# RocketometerPx_9150.net
KiCad netlist of a schematic drawn in EAGLE
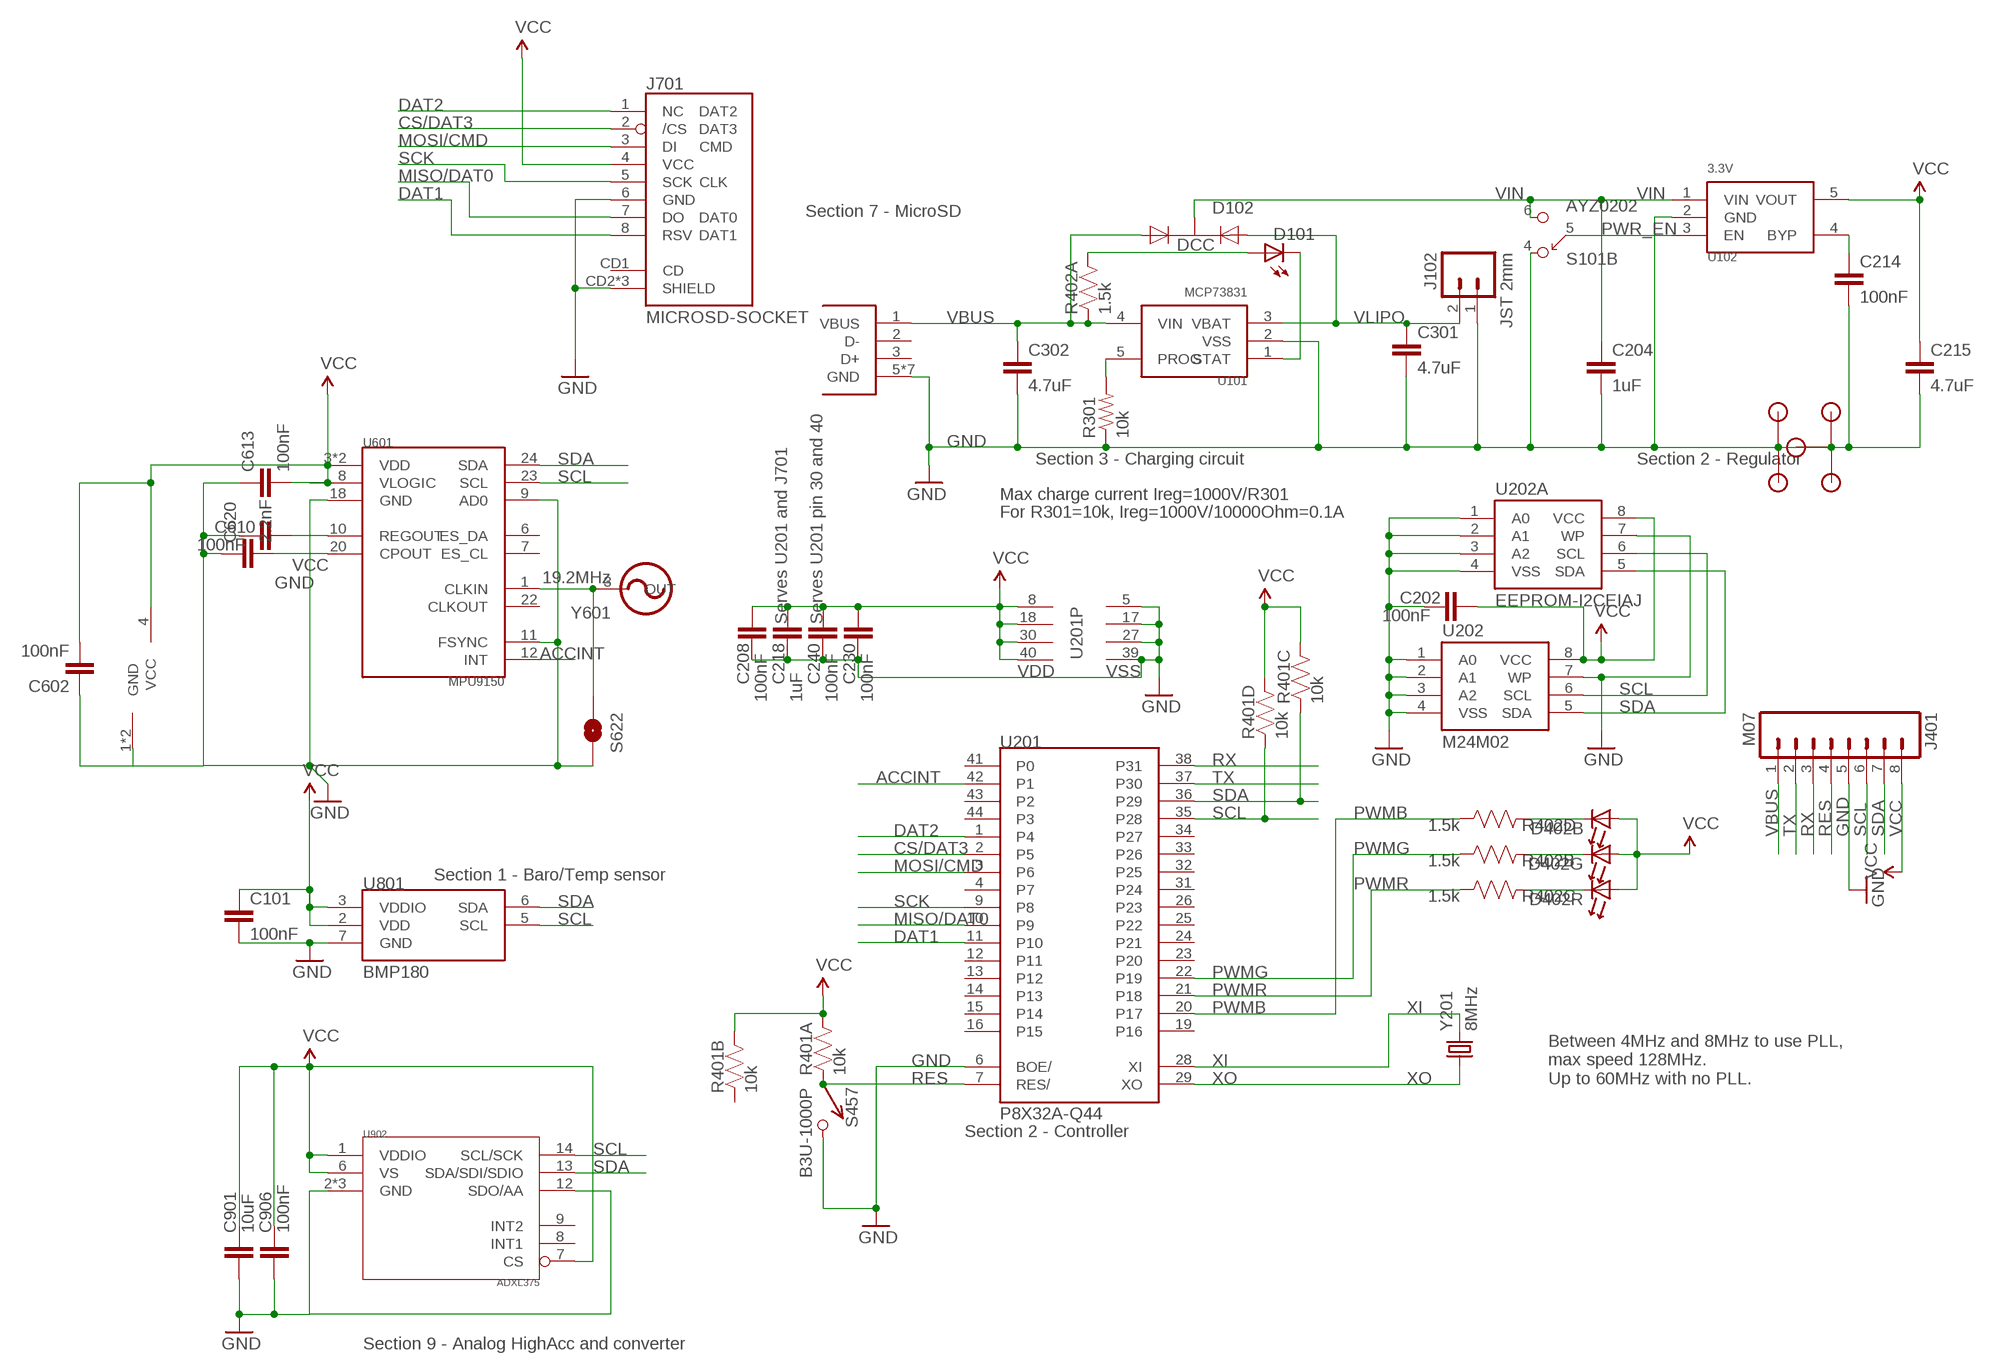
[diagram p0: schematic, sheet 1]

(export (version "E")
  (design (tool "Eeschema 10.0.6"))
  (components
    (comp (ref "C101")
      (value "100nF")
      (footprint "eagle-import:0402-CAP")
      (libsource (lib "eagle-import") (part "CAP0402-CAP"))
    )
    (comp (ref "C202")
      (value "100nF")
      (footprint "eagle-import:0402-CAP")
      (libsource (lib "eagle-import") (part "CAP0402-CAP"))
    )
    (comp (ref "C204")
      (value "1uF")
      (footprint "eagle-import:0402-CAP")
      (libsource (lib "eagle-import") (part "CAP0402-CAP"))
    )
    (comp (ref "C208")
      (value "100nF")
      (footprint "eagle-import:0402-CAP")
      (libsource (lib "eagle-import") (part "CAP0402-CAP"))
    )
    (comp (ref "C214")
      (value "100nF")
      (footprint "eagle-import:0402-CAP")
      (libsource (lib "eagle-import") (part "CAP0402-CAP"))
    )
    (comp (ref "C215")
      (value "4.7uF")
      (footprint "eagle-import:0402-CAP")
      (libsource (lib "eagle-import") (part "CAP0402-CAP"))
    )
    (comp (ref "C218")
      (value "1uF")
      (footprint "eagle-import:0402-CAP")
      (libsource (lib "eagle-import") (part "CAP0402-CAP"))
    )
    (comp (ref "C230")
      (value "100nF")
      (footprint "eagle-import:0402-CAP")
      (libsource (lib "eagle-import") (part "CAP0402-CAP"))
    )
    (comp (ref "C240")
      (value "100nF")
      (footprint "eagle-import:0402-CAP")
      (libsource (lib "eagle-import") (part "CAP0402-CAP"))
    )
    (comp (ref "C301")
      (value "4.7uF")
      (footprint "eagle-import:0402-CAP")
      (libsource (lib "eagle-import") (part "CAP0402-CAP"))
    )
    (comp (ref "C302")
      (value "4.7uF")
      (footprint "eagle-import:0402-CAP")
      (libsource (lib "eagle-import") (part "CAP0402-CAP"))
    )
    (comp (ref "C602")
      (value "100nF")
      (footprint "eagle-import:0402-CAP")
      (libsource (lib "eagle-import") (part "CAP0402-CAP"))
    )
    (comp (ref "C610")
      (value "100nF")
      (footprint "eagle-import:0402-CAP")
      (libsource (lib "eagle-import") (part "CAP0402-CAP"))
    )
    (comp (ref "C613")
      (value "100nF")
      (footprint "eagle-import:0402-CAP")
      (libsource (lib "eagle-import") (part "CAP0402-CAP"))
    )
    (comp (ref "C620")
      (value "2.2nF")
      (footprint "eagle-import:0402-CAP")
      (libsource (lib "eagle-import") (part "CAP0402-CAP"))
    )
    (comp (ref "C901")
      (value "10uF")
      (footprint "eagle-import:0603-CAP")
      (libsource (lib "eagle-import") (part "CAP0603-CAP"))
    )
    (comp (ref "C906")
      (value "100nF")
      (footprint "eagle-import:0402-CAP")
      (libsource (lib "eagle-import") (part "SparkFun-Passives_CAP0402-CAP"))
    )
    (comp (ref "D101")
      (value "YELLOW")
      (footprint "eagle-import:LED-0603")
      (libsource (lib "eagle-import") (part "LED0603"))
    )
    (comp (ref "D102")
      (value "DCC")
      (footprint "eagle-import:SOT-23-3")
      (libsource (lib "eagle-import") (part "PMEG2005CT"))
    )
    (comp (ref "D402")
      (value "SMLP36RGB2W(R)")
      (footprint "eagle-import:SMLP36")
      (libsource (lib "eagle-import") (part "SMLP36RGB2W(R)"))
    )
    (comp (ref "J101")
      (value "USB_MICROB_JSTGCT")
      (footprint "eagle-import:USB_MICROB_3075")
      (libsource (lib "eagle-import") (part "USB_MICROB_JSTGCT"))
    )
    (comp (ref "J102")
      (value "JST 2mm")
      (footprint "eagle-import:JST-2-SMD")
      (libsource (lib "eagle-import") (part "M02-JST-2MM-SMT"))
    )
    (comp (ref "J401")
      (value "M07")
      (footprint "eagle-import:1X08")
      (libsource (lib "eagle-import") (part "M081X08"))
    )
    (comp (ref "J701")
      (value "MICROSD-SOCKET")
      (footprint "eagle-import:MICROSD-SOCKET-PP")
      (libsource (lib "eagle-import") (part "MICROSD-SOCKET"))
    )
    (comp (ref "JP1")
      (value "STANDOFF")
      (footprint "eagle-import:STANDOFF")
      (libsource (lib "eagle-import") (part "STANDOFF"))
    )
    (comp (ref "JP2")
      (value "STANDOFF")
      (footprint "eagle-import:STANDOFF")
      (libsource (lib "eagle-import") (part "STANDOFF"))
    )
    (comp (ref "JP3")
      (value "STANDOFF")
      (footprint "eagle-import:STANDOFF")
      (libsource (lib "eagle-import") (part "STANDOFF"))
    )
    (comp (ref "JP4")
      (value "STANDOFF")
      (footprint "eagle-import:STANDOFF")
      (libsource (lib "eagle-import") (part "STANDOFF"))
    )
    (comp (ref "JP5")
      (value "STANDOFF")
      (footprint "eagle-import:STANDOFF")
      (libsource (lib "eagle-import") (part "STANDOFF"))
    )
    (comp (ref "R301")
      (value "10k")
      (footprint "eagle-import:0402-RES")
      (libsource (lib "eagle-import") (part "RESISTOR0402-RES"))
    )
    (comp (ref "R401")
      (value "10k")
      (footprint "eagle-import:CRA04")
      (fields (field (name "DIGIKEY") "CRA4S810KCT-ND"))
      (libsource (lib "eagle-import") (part "RP404"))
    )
    (comp (ref "R402")
      (value "1.5k")
      (footprint "eagle-import:CRA04")
      (fields (field (name "DIGIKEY") "CRA4S81.5KCT-ND"))
      (libsource (lib "eagle-import") (part "RP404"))
    )
    (comp (ref "S101")
      (value "AYZ0202")
      (footprint "eagle-import:AYZ0202")
      (libsource (lib "eagle-import") (part "AYZ0202"))
    )
    (comp (ref "S457")
      (value "B3U-1000P")
      (footprint "eagle-import:B3U-1000P")
      (libsource (lib "eagle-import") (part "B3U-1000P"))
    )
    (comp (ref "S622")
      (value "SOLDERJUMPERNO")
      (footprint "eagle-import:SJ_2S-NO")
      (libsource (lib "eagle-import") (part "SOLDERJUMPERNO"))
    )
    (comp (ref "U101")
      (value "MCP73831")
      (footprint "eagle-import:SOT-23-5")
      (libsource (lib "eagle-import") (part "MCP73831"))
    )
    (comp (ref "U102")
      (value "3.3V")
      (footprint "eagle-import:SOT-23-5")
      (libsource (lib "eagle-import") (part "MIC5319D5"))
    )
    (comp (ref "U201")
      (value "P8X32A-Q44")
      (footprint "eagle-import:P8X32A-Q44")
      (fields (field (name "DIGIKEY") "P8X32A-Q44-ND"))
      (libsource (lib "eagle-import") (part "P8X32A-Q44"))
    )
    (comp (ref "U202")
      (value "M24M02")
      (footprint "eagle-import:SO8N")
      (libsource (lib "eagle-import") (part "EEPROM-I2C"))
    )
    (comp (ref "U202A")
      (value "EEPROM-I2CEIAJ")
      (footprint "eagle-import:SO08-EIAJ")
      (libsource (lib "eagle-import") (part "EEPROM-I2CEIAJ"))
    )
    (comp (ref "U601")
      (value "MPU9150")
      (footprint "eagle-import:MPU60X0")
      (libsource (lib "eagle-import") (part "MPU6050"))
    )
    (comp (ref "U801")
      (value "BMP180")
      (footprint "eagle-import:BMP180")
      (libsource (lib "eagle-import") (part "BMP180"))
    )
    (comp (ref "U902")
      (value "ADXL375")
      (footprint "eagle-import:ADXL375")
      (libsource (lib "eagle-import") (part "ADXL375"))
    )
    (comp (ref "Y201")
      (value "8MHz")
      (footprint "eagle-import:CRYSTAL_SMD_3_2MM_2_5MM")
      (libsource (lib "eagle-import") (part "NX3225GD"))
    )
    (comp (ref "Y601")
      (value "19.2MHz")
      (footprint "eagle-import:CRYSTAL_SMD_5MM_3_2MM")
      (libsource (lib "eagle-import") (part "OSCILLATORM532"))
    )
  )
  (nets
    (net (code "1") (name "/ACCINT") (class "Default")
      (node (ref "U201") (pin "42") (pinfunction "P1_42") (pintype "bidirectional"))
      (node (ref "U601") (pin "12") (pinfunction "INT_12") (pintype "bidirectional"))
    )
    (net (code "2") (name "/CS{slash}DAT3") (class "Default")
      (node (ref "J701") (pin "2") (pinfunction "/CS_2") (pintype "bidirectional"))
      (node (ref "U201") (pin "2") (pinfunction "P5_2") (pintype "bidirectional"))
    )
    (net (code "3") (name "/DAT1") (class "Default")
      (node (ref "J701") (pin "8") (pinfunction "RSV_8") (pintype "bidirectional"))
      (node (ref "U201") (pin "11") (pinfunction "P10_11") (pintype "bidirectional"))
    )
    (net (code "4") (name "/DAT2") (class "Default")
      (node (ref "J701") (pin "1") (pinfunction "NC_1") (pintype "bidirectional"))
      (node (ref "U201") (pin "1") (pinfunction "P4_1") (pintype "bidirectional"))
    )
    (net (code "5") (name "/MISO{slash}DAT0") (class "Default")
      (node (ref "J701") (pin "7") (pinfunction "DO_7") (pintype "bidirectional"))
      (node (ref "U201") (pin "10") (pinfunction "P9_10") (pintype "bidirectional"))
    )
    (net (code "6") (name "/MOSI{slash}CMD") (class "Default")
      (node (ref "J701") (pin "3") (pinfunction "DI_3") (pintype "bidirectional"))
      (node (ref "U201") (pin "3") (pinfunction "P6_3") (pintype "bidirectional"))
    )
    (net (code "7") (name "/PWMB") (class "Default")
      (node (ref "R402") (pin "4") (pinfunction "1_4") (pintype "passive"))
      (node (ref "U201") (pin "20") (pinfunction "P17_20") (pintype "bidirectional"))
    )
    (net (code "8") (name "/PWMG") (class "Default")
      (node (ref "R402") (pin "2") (pinfunction "1_2") (pintype "passive"))
      (node (ref "U201") (pin "22") (pinfunction "P19_22") (pintype "bidirectional"))
    )
    (net (code "9") (name "/PWMR") (class "Default")
      (node (ref "R402") (pin "3") (pinfunction "1_3") (pintype "passive"))
      (node (ref "U201") (pin "21") (pinfunction "P18_21") (pintype "bidirectional"))
    )
    (net (code "10") (name "/PWR_EN") (class "Default")
      (node (ref "S101") (pin "5") (pinfunction "P$3_5") (pintype "bidirectional"))
      (node (ref "U102") (pin "3") (pinfunction "EN_3") (pintype "bidirectional"))
    )
    (net (code "11") (name "/RES") (class "Default")
      (node (ref "J401") (pin "4") (pinfunction "4_4") (pintype "passive"))
      (node (ref "R401") (pin "1") (pinfunction "1_1") (pintype "passive"))
      (node (ref "S457") (pin "P$1") (pinfunction "1_P$1") (pintype "bidirectional"))
      (node (ref "U201") (pin "7") (pinfunction "RES/_7") (pintype "bidirectional"))
    )
    (net (code "12") (name "/RX") (class "Default")
      (node (ref "J401") (pin "3") (pinfunction "3_3") (pintype "passive"))
      (node (ref "U201") (pin "38") (pinfunction "P31_38") (pintype "bidirectional"))
    )
    (net (code "13") (name "/SCK") (class "Default")
      (node (ref "J701") (pin "5") (pinfunction "SCK_5") (pintype "bidirectional"))
      (node (ref "U201") (pin "9") (pinfunction "P8_9") (pintype "bidirectional"))
    )
    (net (code "14") (name "/SCL") (class "Default")
      (node (ref "J401") (pin "6") (pinfunction "6_6") (pintype "passive"))
      (node (ref "R401") (pin "4") (pinfunction "1_4") (pintype "passive"))
      (node (ref "U201") (pin "35") (pinfunction "P28_35") (pintype "bidirectional"))
      (node (ref "U202") (pin "6") (pinfunction "SCL_6") (pintype "bidirectional"))
      (node (ref "U202A") (pin "6") (pinfunction "SCL_6") (pintype "bidirectional"))
      (node (ref "U601") (pin "23") (pinfunction "SCL_23") (pintype "bidirectional"))
      (node (ref "U801") (pin "5") (pinfunction "SCL_5") (pintype "input"))
      (node (ref "U902") (pin "14") (pinfunction "SCL/SCK_14") (pintype "input"))
    )
    (net (code "15") (name "/SDA") (class "Default")
      (node (ref "J401") (pin "7") (pinfunction "7_7") (pintype "passive"))
      (node (ref "R401") (pin "3") (pinfunction "1_3") (pintype "passive"))
      (node (ref "U201") (pin "36") (pinfunction "P29_36") (pintype "bidirectional"))
      (node (ref "U202") (pin "5") (pinfunction "SDA_5") (pintype "bidirectional"))
      (node (ref "U202A") (pin "5") (pinfunction "SDA_5") (pintype "bidirectional"))
      (node (ref "U601") (pin "24") (pinfunction "SDA_24") (pintype "bidirectional"))
      (node (ref "U801") (pin "6") (pinfunction "SDA_6") (pintype "bidirectional"))
      (node (ref "U902") (pin "13") (pinfunction "SDA/SDI/SDIO_13") (pintype "bidirectional"))
    )
    (net (code "16") (name "/TX") (class "Default")
      (node (ref "J401") (pin "2") (pinfunction "2_2") (pintype "passive"))
      (node (ref "U201") (pin "37") (pinfunction "P30_37") (pintype "bidirectional"))
    )
    (net (code "17") (name "/VBUS") (class "Default")
      (node (ref "C302") (pin "1") (pinfunction "1_1") (pintype "passive"))
      (node (ref "D102") (pin "1") (pinfunction "A1_1") (pintype "passive"))
      (node (ref "J101") (pin "1") (pinfunction "VBUS_1") (pintype "bidirectional"))
      (node (ref "J401") (pin "1") (pinfunction "1_1") (pintype "passive"))
      (node (ref "R402") (pin "1") (pinfunction "1_1") (pintype "passive"))
      (node (ref "U101") (pin "4") (pinfunction "VIN_4") (pintype "power_in"))
    )
    (net (code "18") (name "/VIN") (class "Default")
      (node (ref "C204") (pin "1") (pinfunction "1_1") (pintype "passive"))
      (node (ref "D102") (pin "3") (pinfunction "K_3") (pintype "passive"))
      (node (ref "S101") (pin "6") (pinfunction "P$2_6") (pintype "bidirectional"))
      (node (ref "U102") (pin "1") (pinfunction "VIN_1") (pintype "bidirectional"))
    )
    (net (code "19") (name "/VLIPO") (class "Default")
      (node (ref "C301") (pin "1") (pinfunction "1_1") (pintype "passive"))
      (node (ref "D102") (pin "2") (pinfunction "A2_2") (pintype "passive"))
      (node (ref "J102") (pin "2") (pinfunction "2_2") (pintype "passive"))
      (node (ref "U101") (pin "3") (pinfunction "VBAT_3") (pintype "power_in"))
    )
    (net (code "20") (name "/XI") (class "Default")
      (node (ref "U201") (pin "28") (pinfunction "XI_28") (pintype "input"))
      (node (ref "Y201") (pin "2") (pinfunction "2_2") (pintype "passive"))
    )
    (net (code "21") (name "/XO") (class "Default")
      (node (ref "U201") (pin "29") (pinfunction "XO_29") (pintype "output"))
      (node (ref "Y201") (pin "1") (pinfunction "1_1") (pintype "passive"))
    )
    (net (code "22") (name "GND") (class "Default")
      (node (ref "C101") (pin "2") (pinfunction "2_2") (pintype "passive"))
      (node (ref "C202") (pin "2") (pinfunction "2_2") (pintype "passive"))
      (node (ref "C204") (pin "2") (pinfunction "2_2") (pintype "passive"))
      (node (ref "C208") (pin "2") (pinfunction "2_2") (pintype "passive"))
      (node (ref "C214") (pin "2") (pinfunction "2_2") (pintype "passive"))
      (node (ref "C215") (pin "2") (pinfunction "2_2") (pintype "passive"))
      (node (ref "C218") (pin "2") (pinfunction "2_2") (pintype "passive"))
      (node (ref "C230") (pin "2") (pinfunction "2_2") (pintype "passive"))
      (node (ref "C240") (pin "2") (pinfunction "2_2") (pintype "passive"))
      (node (ref "C301") (pin "2") (pinfunction "2_2") (pintype "passive"))
      (node (ref "C302") (pin "2") (pinfunction "2_2") (pintype "passive"))
      (node (ref "C602") (pin "1") (pinfunction "1_1") (pintype "passive"))
      (node (ref "C610") (pin "2") (pinfunction "2_2") (pintype "passive"))
      (node (ref "C613") (pin "1") (pinfunction "1_1") (pintype "passive"))
      (node (ref "C620") (pin "1") (pinfunction "1_1") (pintype "passive"))
      (node (ref "C901") (pin "2") (pinfunction "2_2") (pintype "passive"))
      (node (ref "C906") (pin "2") (pinfunction "2_2") (pintype "passive"))
      (node (ref "J101") (pin "5") (pinfunction "GND_5") (pintype "bidirectional"))
      (node (ref "J101") (pin "P$1") (pinfunction "GND_P$1") (pintype "bidirectional"))
      (node (ref "J101") (pin "P$10") (pinfunction "GND_P$10") (pintype "bidirectional"))
      (node (ref "J101") (pin "P$2") (pinfunction "GND_P$2") (pintype "bidirectional"))
      (node (ref "J101") (pin "P$3") (pinfunction "GND_P$3") (pintype "bidirectional"))
      (node (ref "J101") (pin "P$4") (pinfunction "GND_P$4") (pintype "bidirectional"))
      (node (ref "J101") (pin "P$8") (pinfunction "GND_P$8") (pintype "bidirectional"))
      (node (ref "J102") (pin "1") (pinfunction "1_1") (pintype "passive"))
      (node (ref "J401") (pin "5") (pinfunction "5_5") (pintype "passive"))
      (node (ref "J701") (pin "6") (pinfunction "GND_6") (pintype "bidirectional"))
      (node (ref "J701") (pin "CD2") (pinfunction "SHIELD_CD2") (pintype "bidirectional"))
      (node (ref "J701") (pin "GND1") (pinfunction "SHIELD_GND1") (pintype "bidirectional"))
      (node (ref "J701") (pin "GND3") (pinfunction "SHIELD_GND3") (pintype "bidirectional"))
      (node (ref "JP1") (pin "P$1") (pinfunction "P$1_P$1") (pintype "bidirectional"))
      (node (ref "JP2") (pin "P$1") (pinfunction "P$1_P$1") (pintype "bidirectional"))
      (node (ref "JP3") (pin "P$1") (pinfunction "P$1_P$1") (pintype "bidirectional"))
      (node (ref "JP4") (pin "P$1") (pinfunction "P$1_P$1") (pintype "bidirectional"))
      (node (ref "JP5") (pin "P$1") (pinfunction "P$1_P$1") (pintype "bidirectional"))
      (node (ref "R301") (pin "1") (pinfunction "1_1") (pintype "passive"))
      (node (ref "S101") (pin "4") (pinfunction "P$1_4") (pintype "bidirectional"))
      (node (ref "S457") (pin "P$2") (pinfunction "2_P$2") (pintype "bidirectional"))
      (node (ref "S622") (pin "2") (pinfunction "2_2") (pintype "passive"))
      (node (ref "U101") (pin "2") (pinfunction "VSS_2") (pintype "power_in"))
      (node (ref "U102") (pin "2") (pinfunction "GND_2") (pintype "bidirectional"))
      (node (ref "U201") (pin "17") (pinfunction "VSS_17") (pintype "power_in"))
      (node (ref "U201") (pin "27") (pinfunction "VSS_27") (pintype "power_in"))
      (node (ref "U201") (pin "39") (pinfunction "VSS_39") (pintype "power_in"))
      (node (ref "U201") (pin "5") (pinfunction "VSS_5") (pintype "power_in"))
      (node (ref "U201") (pin "6") (pinfunction "BOE/_6") (pintype "input"))
      (node (ref "U202") (pin "1") (pinfunction "A0_1") (pintype "bidirectional"))
      (node (ref "U202") (pin "2") (pinfunction "A1_2") (pintype "bidirectional"))
      (node (ref "U202") (pin "3") (pinfunction "A2_3") (pintype "bidirectional"))
      (node (ref "U202") (pin "4") (pinfunction "VSS_4") (pintype "power_in"))
      (node (ref "U202") (pin "7") (pinfunction "WP_7") (pintype "bidirectional"))
      (node (ref "U202A") (pin "1") (pinfunction "A0_1") (pintype "bidirectional"))
      (node (ref "U202A") (pin "2") (pinfunction "A1_2") (pintype "bidirectional"))
      (node (ref "U202A") (pin "3") (pinfunction "A2_3") (pintype "bidirectional"))
      (node (ref "U202A") (pin "4") (pinfunction "VSS_4") (pintype "power_in"))
      (node (ref "U202A") (pin "7") (pinfunction "WP_7") (pintype "bidirectional"))
      (node (ref "U601") (pin "11") (pinfunction "FSYNC_11") (pintype "bidirectional"))
      (node (ref "U601") (pin "18") (pinfunction "GND_18") (pintype "bidirectional"))
      (node (ref "U601") (pin "9") (pinfunction "AD0_9") (pintype "bidirectional"))
      (node (ref "U801") (pin "7") (pinfunction "GND_7") (pintype "power_in"))
      (node (ref "U902") (pin "12") (pinfunction "SDO/AA_12") (pintype "bidirectional"))
      (node (ref "U902") (pin "2") (pinfunction "GND_2") (pintype "power_in"))
      (node (ref "U902") (pin "4") (pinfunction "GND_4") (pintype "power_in"))
      (node (ref "U902") (pin "5") (pinfunction "GND_5") (pintype "power_in"))
      (node (ref "Y601") (pin "1") (pinfunction "GND_1") (pintype "bidirectional"))
      (node (ref "Y601") (pin "2") (pinfunction "GND_2") (pintype "bidirectional"))
    )
    (net (code "23") (name "Net-(D402A-C)") (class "Default")
      (node (ref "D402") (pin "1") (pinfunction "C_1") (pintype "passive"))
      (node (ref "R402") (pin "5") (pinfunction "2_5") (pintype "passive"))
    )
    (net (code "24") (name "Net-(D402B-C)") (class "Default")
      (node (ref "D402") (pin "5") (pinfunction "C_5") (pintype "passive"))
      (node (ref "R402") (pin "7") (pinfunction "2_7") (pintype "passive"))
    )
    (net (code "25") (name "Net-(D402C-C)") (class "Default")
      (node (ref "D402") (pin "3") (pinfunction "C_3") (pintype "passive"))
      (node (ref "R402") (pin "6") (pinfunction "2_6") (pintype "passive"))
    )
    (net (code "26") (name "Net-(R402A-2)") (class "Default")
      (node (ref "D101") (pin "A") (pinfunction "A_A") (pintype "passive"))
      (node (ref "R402") (pin "8") (pinfunction "2_8") (pintype "passive"))
    )
    (net (code "27") (name "Net-(U101-PROG)") (class "Default")
      (node (ref "R301") (pin "2") (pinfunction "2_2") (pintype "passive"))
      (node (ref "U101") (pin "5") (pinfunction "PROG_5") (pintype "passive"))
    )
    (net (code "28") (name "Net-(U101-STAT)") (class "Default")
      (node (ref "D101") (pin "C") (pinfunction "C_C") (pintype "passive"))
      (node (ref "U101") (pin "1") (pinfunction "STAT_1") (pintype "bidirectional"))
    )
    (net (code "29") (name "Net-(U102-BYP)") (class "Default")
      (node (ref "C214") (pin "1") (pinfunction "1_1") (pintype "passive"))
      (node (ref "U102") (pin "4") (pinfunction "BYP_4") (pintype "bidirectional"))
    )
    (net (code "30") (name "Net-(U601-CLKIN)") (class "Default")
      (node (ref "S622") (pin "1") (pinfunction "1_1") (pintype "passive"))
      (node (ref "U601") (pin "1") (pinfunction "CLKIN_1") (pintype "bidirectional"))
      (node (ref "Y601") (pin "3") (pinfunction "OUT_3") (pintype "bidirectional"))
    )
    (net (code "31") (name "Net-(U601-CPOUT)") (class "Default")
      (node (ref "C620") (pin "2") (pinfunction "2_2") (pintype "passive"))
      (node (ref "U601") (pin "20") (pinfunction "CPOUT_20") (pintype "bidirectional"))
    )
    (net (code "32") (name "Net-(U601-REGOUT)") (class "Default")
      (node (ref "C610") (pin "1") (pinfunction "1_1") (pintype "passive"))
      (node (ref "U601") (pin "10") (pinfunction "REGOUT_10") (pintype "bidirectional"))
    )
    (net (code "33") (name "VCC") (class "Default")
      (node (ref "C101") (pin "1") (pinfunction "1_1") (pintype "passive"))
      (node (ref "C202") (pin "1") (pinfunction "1_1") (pintype "passive"))
      (node (ref "C208") (pin "1") (pinfunction "1_1") (pintype "passive"))
      (node (ref "C215") (pin "1") (pinfunction "1_1") (pintype "passive"))
      (node (ref "C218") (pin "1") (pinfunction "1_1") (pintype "passive"))
      (node (ref "C230") (pin "1") (pinfunction "1_1") (pintype "passive"))
      (node (ref "C240") (pin "1") (pinfunction "1_1") (pintype "passive"))
      (node (ref "C602") (pin "2") (pinfunction "2_2") (pintype "passive"))
      (node (ref "C613") (pin "2") (pinfunction "2_2") (pintype "passive"))
      (node (ref "C901") (pin "1") (pinfunction "1_1") (pintype "passive"))
      (node (ref "C906") (pin "1") (pinfunction "1_1") (pintype "passive"))
      (node (ref "D402") (pin "2") (pinfunction "A_2") (pintype "passive"))
      (node (ref "D402") (pin "4") (pinfunction "A_4") (pintype "passive"))
      (node (ref "D402") (pin "6") (pinfunction "A_6") (pintype "passive"))
      (node (ref "J401") (pin "8") (pinfunction "8_8") (pintype "passive"))
      (node (ref "J701") (pin "4") (pinfunction "VCC_4") (pintype "bidirectional"))
      (node (ref "R401") (pin "5") (pinfunction "2_5") (pintype "passive"))
      (node (ref "R401") (pin "6") (pinfunction "2_6") (pintype "passive"))
      (node (ref "R401") (pin "7") (pinfunction "2_7") (pintype "passive"))
      (node (ref "R401") (pin "8") (pinfunction "2_8") (pintype "passive"))
      (node (ref "U102") (pin "5") (pinfunction "VOUT_5") (pintype "bidirectional"))
      (node (ref "U201") (pin "18") (pinfunction "VDD_18") (pintype "power_in"))
      (node (ref "U201") (pin "30") (pinfunction "VDD_30") (pintype "power_in"))
      (node (ref "U201") (pin "40") (pinfunction "VDD_40") (pintype "power_in"))
      (node (ref "U201") (pin "8") (pinfunction "VDD_8") (pintype "power_in"))
      (node (ref "U202") (pin "8") (pinfunction "VCC_8") (pintype "power_in"))
      (node (ref "U202A") (pin "8") (pinfunction "VCC_8") (pintype "power_in"))
      (node (ref "U601") (pin "13") (pinfunction "VDD_13") (pintype "bidirectional"))
      (node (ref "U601") (pin "3") (pinfunction "VDD_3") (pintype "bidirectional"))
      (node (ref "U601") (pin "8") (pinfunction "VLOGIC_8") (pintype "bidirectional"))
      (node (ref "U801") (pin "2") (pinfunction "VDD_2") (pintype "power_in"))
      (node (ref "U801") (pin "3") (pinfunction "VDDIO_3") (pintype "power_in"))
      (node (ref "U902") (pin "1") (pinfunction "VDDIO_1") (pintype "power_in"))
      (node (ref "U902") (pin "6") (pinfunction "VS_6") (pintype "power_in"))
      (node (ref "U902") (pin "7") (pinfunction "CS_7") (pintype "input"))
      (node (ref "Y601") (pin "4") (pinfunction "VCC_4") (pintype "bidirectional"))
    )
    (net (code "34") (name "unconnected-(J101-D+-Pad3)") (class "Default")
      (node (ref "J101") (pin "3") (pinfunction "D+_3") (pintype "bidirectional"))
    )
    (net (code "35") (name "unconnected-(J101-D--Pad2)") (class "Default")
      (node (ref "J101") (pin "2") (pinfunction "D-_2") (pintype "bidirectional"))
    )
    (net (code "36") (name "unconnected-(J701-CD-PadCD1)") (class "Default")
      (node (ref "J701") (pin "CD1") (pinfunction "CD_CD1") (pintype "bidirectional"))
    )
    (net (code "37") (name "unconnected-(R401B-1-Pad2)") (class "Default")
      (node (ref "R401") (pin "2") (pinfunction "1_2") (pintype "passive"))
    )
    (net (code "38") (name "unconnected-(U201B-P0-Pad41)") (class "Default")
      (node (ref "U201") (pin "41") (pinfunction "P0_41") (pintype "bidirectional"))
    )
    (net (code "39") (name "unconnected-(U201B-P2-Pad43)") (class "Default")
      (node (ref "U201") (pin "43") (pinfunction "P2_43") (pintype "bidirectional"))
    )
    (net (code "40") (name "unconnected-(U201B-P3-Pad44)") (class "Default")
      (node (ref "U201") (pin "44") (pinfunction "P3_44") (pintype "bidirectional"))
    )
    (net (code "41") (name "unconnected-(U201B-P7-Pad4)") (class "Default")
      (node (ref "U201") (pin "4") (pinfunction "P7_4") (pintype "bidirectional"))
    )
    (net (code "42") (name "unconnected-(U201B-P11-Pad12)") (class "Default")
      (node (ref "U201") (pin "12") (pinfunction "P11_12") (pintype "bidirectional"))
    )
    (net (code "43") (name "unconnected-(U201B-P12-Pad13)") (class "Default")
      (node (ref "U201") (pin "13") (pinfunction "P12_13") (pintype "bidirectional"))
    )
    (net (code "44") (name "unconnected-(U201B-P13-Pad14)") (class "Default")
      (node (ref "U201") (pin "14") (pinfunction "P13_14") (pintype "bidirectional"))
    )
    (net (code "45") (name "unconnected-(U201B-P14-Pad15)") (class "Default")
      (node (ref "U201") (pin "15") (pinfunction "P14_15") (pintype "bidirectional"))
    )
    (net (code "46") (name "unconnected-(U201B-P15-Pad16)") (class "Default")
      (node (ref "U201") (pin "16") (pinfunction "P15_16") (pintype "bidirectional"))
    )
    (net (code "47") (name "unconnected-(U201B-P16-Pad19)") (class "Default")
      (node (ref "U201") (pin "19") (pinfunction "P16_19") (pintype "bidirectional"))
    )
    (net (code "48") (name "unconnected-(U201B-P20-Pad23)") (class "Default")
      (node (ref "U201") (pin "23") (pinfunction "P20_23") (pintype "bidirectional"))
    )
    (net (code "49") (name "unconnected-(U201B-P21-Pad24)") (class "Default")
      (node (ref "U201") (pin "24") (pinfunction "P21_24") (pintype "bidirectional"))
    )
    (net (code "50") (name "unconnected-(U201B-P22-Pad25)") (class "Default")
      (node (ref "U201") (pin "25") (pinfunction "P22_25") (pintype "bidirectional"))
    )
    (net (code "51") (name "unconnected-(U201B-P23-Pad26)") (class "Default")
      (node (ref "U201") (pin "26") (pinfunction "P23_26") (pintype "bidirectional"))
    )
    (net (code "52") (name "unconnected-(U201B-P24-Pad31)") (class "Default")
      (node (ref "U201") (pin "31") (pinfunction "P24_31") (pintype "bidirectional"))
    )
    (net (code "53") (name "unconnected-(U201B-P25-Pad32)") (class "Default")
      (node (ref "U201") (pin "32") (pinfunction "P25_32") (pintype "bidirectional"))
    )
    (net (code "54") (name "unconnected-(U201B-P26-Pad33)") (class "Default")
      (node (ref "U201") (pin "33") (pinfunction "P26_33") (pintype "bidirectional"))
    )
    (net (code "55") (name "unconnected-(U201B-P27-Pad34)") (class "Default")
      (node (ref "U201") (pin "34") (pinfunction "P27_34") (pintype "bidirectional"))
    )
    (net (code "56") (name "unconnected-(U601-CLKOUT-Pad22)") (class "Default")
      (node (ref "U601") (pin "22") (pinfunction "CLKOUT_22") (pintype "bidirectional"))
    )
    (net (code "57") (name "unconnected-(U601-ES_CL-Pad7)") (class "Default")
      (node (ref "U601") (pin "7") (pinfunction "ES_CL_7") (pintype "bidirectional"))
    )
    (net (code "58") (name "unconnected-(U601-ES_DA-Pad6)") (class "Default")
      (node (ref "U601") (pin "6") (pinfunction "ES_DA_6") (pintype "bidirectional"))
    )
    (net (code "59") (name "unconnected-(U902-INT1-Pad8)") (class "Default")
      (node (ref "U902") (pin "8") (pinfunction "INT1_8") (pintype "output"))
    )
    (net (code "60") (name "unconnected-(U902-INT2-Pad9)") (class "Default")
      (node (ref "U902") (pin "9") (pinfunction "INT2_9") (pintype "output"))
    )
  )
)
